# DiveComputer_ButtonPanel.net
KiCad netlist of a schematic drawn in EAGLE
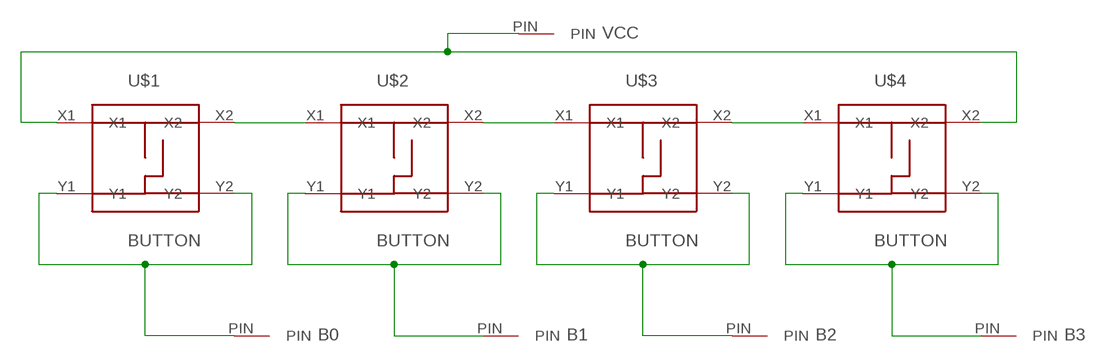
[diagram p0: schematic, sheet 1]

(export (version "E")
  (design (tool "Eeschema 10.0.6"))
  (components
    (comp (ref "B0")
      (value "PIN")
      (footprint "eagle-import:PIN")
      (libsource (lib "eagle-import") (part "PIN"))
    )
    (comp (ref "B1")
      (value "PIN")
      (footprint "eagle-import:PIN")
      (libsource (lib "eagle-import") (part "PIN"))
    )
    (comp (ref "B2")
      (value "PIN")
      (footprint "eagle-import:PIN")
      (libsource (lib "eagle-import") (part "PIN"))
    )
    (comp (ref "B3")
      (value "PIN")
      (footprint "eagle-import:PIN")
      (libsource (lib "eagle-import") (part "PIN"))
    )
    (comp (ref "U$1")
      (value "BUTTON")
      (footprint "eagle-import:BUTTON")
      (libsource (lib "eagle-import") (part "BUTTON"))
    )
    (comp (ref "U$2")
      (value "BUTTON")
      (footprint "eagle-import:BUTTON")
      (libsource (lib "eagle-import") (part "BUTTON"))
    )
    (comp (ref "U$3")
      (value "BUTTON")
      (footprint "eagle-import:BUTTON")
      (libsource (lib "eagle-import") (part "BUTTON"))
    )
    (comp (ref "U$4")
      (value "BUTTON")
      (footprint "eagle-import:BUTTON")
      (libsource (lib "eagle-import") (part "BUTTON"))
    )
    (comp (ref "VCC")
      (value "PIN")
      (footprint "eagle-import:PIN")
      (libsource (lib "eagle-import") (part "PIN"))
    )
  )
  (nets
    (net (code "1") (name "/VCC") (class "Default")
      (node (ref "U$1") (pin "X1") (pinfunction "X1_X1") (pintype "bidirectional"))
      (node (ref "U$1") (pin "X2") (pinfunction "X2_X2") (pintype "bidirectional"))
      (node (ref "U$2") (pin "X1") (pinfunction "X1_X1") (pintype "bidirectional"))
      (node (ref "U$2") (pin "X2") (pinfunction "X2_X2") (pintype "bidirectional"))
      (node (ref "U$3") (pin "X1") (pinfunction "X1_X1") (pintype "bidirectional"))
      (node (ref "U$3") (pin "X2") (pinfunction "X2_X2") (pintype "bidirectional"))
      (node (ref "U$4") (pin "X1") (pinfunction "X1_X1") (pintype "bidirectional"))
      (node (ref "U$4") (pin "X2") (pinfunction "X2_X2") (pintype "bidirectional"))
      (node (ref "VCC") (pin "PIN") (pinfunction "PIN_PIN") (pintype "bidirectional"))
    )
    (net (code "2") (name "Net-(B0-PadPIN)") (class "Default")
      (node (ref "B0") (pin "PIN") (pinfunction "PIN_PIN") (pintype "bidirectional"))
      (node (ref "U$1") (pin "Y1") (pinfunction "Y1_Y1") (pintype "bidirectional"))
      (node (ref "U$1") (pin "Y2") (pinfunction "Y2_Y2") (pintype "bidirectional"))
    )
    (net (code "3") (name "Net-(B1-PadPIN)") (class "Default")
      (node (ref "B1") (pin "PIN") (pinfunction "PIN_PIN") (pintype "bidirectional"))
      (node (ref "U$2") (pin "Y1") (pinfunction "Y1_Y1") (pintype "bidirectional"))
      (node (ref "U$2") (pin "Y2") (pinfunction "Y2_Y2") (pintype "bidirectional"))
    )
    (net (code "4") (name "Net-(B2-PadPIN)") (class "Default")
      (node (ref "B2") (pin "PIN") (pinfunction "PIN_PIN") (pintype "bidirectional"))
      (node (ref "U$3") (pin "Y1") (pinfunction "Y1_Y1") (pintype "bidirectional"))
      (node (ref "U$3") (pin "Y2") (pinfunction "Y2_Y2") (pintype "bidirectional"))
    )
    (net (code "5") (name "Net-(B3-PadPIN)") (class "Default")
      (node (ref "B3") (pin "PIN") (pinfunction "PIN_PIN") (pintype "bidirectional"))
      (node (ref "U$4") (pin "Y1") (pinfunction "Y1_Y1") (pintype "bidirectional"))
      (node (ref "U$4") (pin "Y2") (pinfunction "Y2_Y2") (pintype "bidirectional"))
    )
  )
)
